# keyMANDevices.net
KiCad netlist of a schematic drawn in Altium Designer
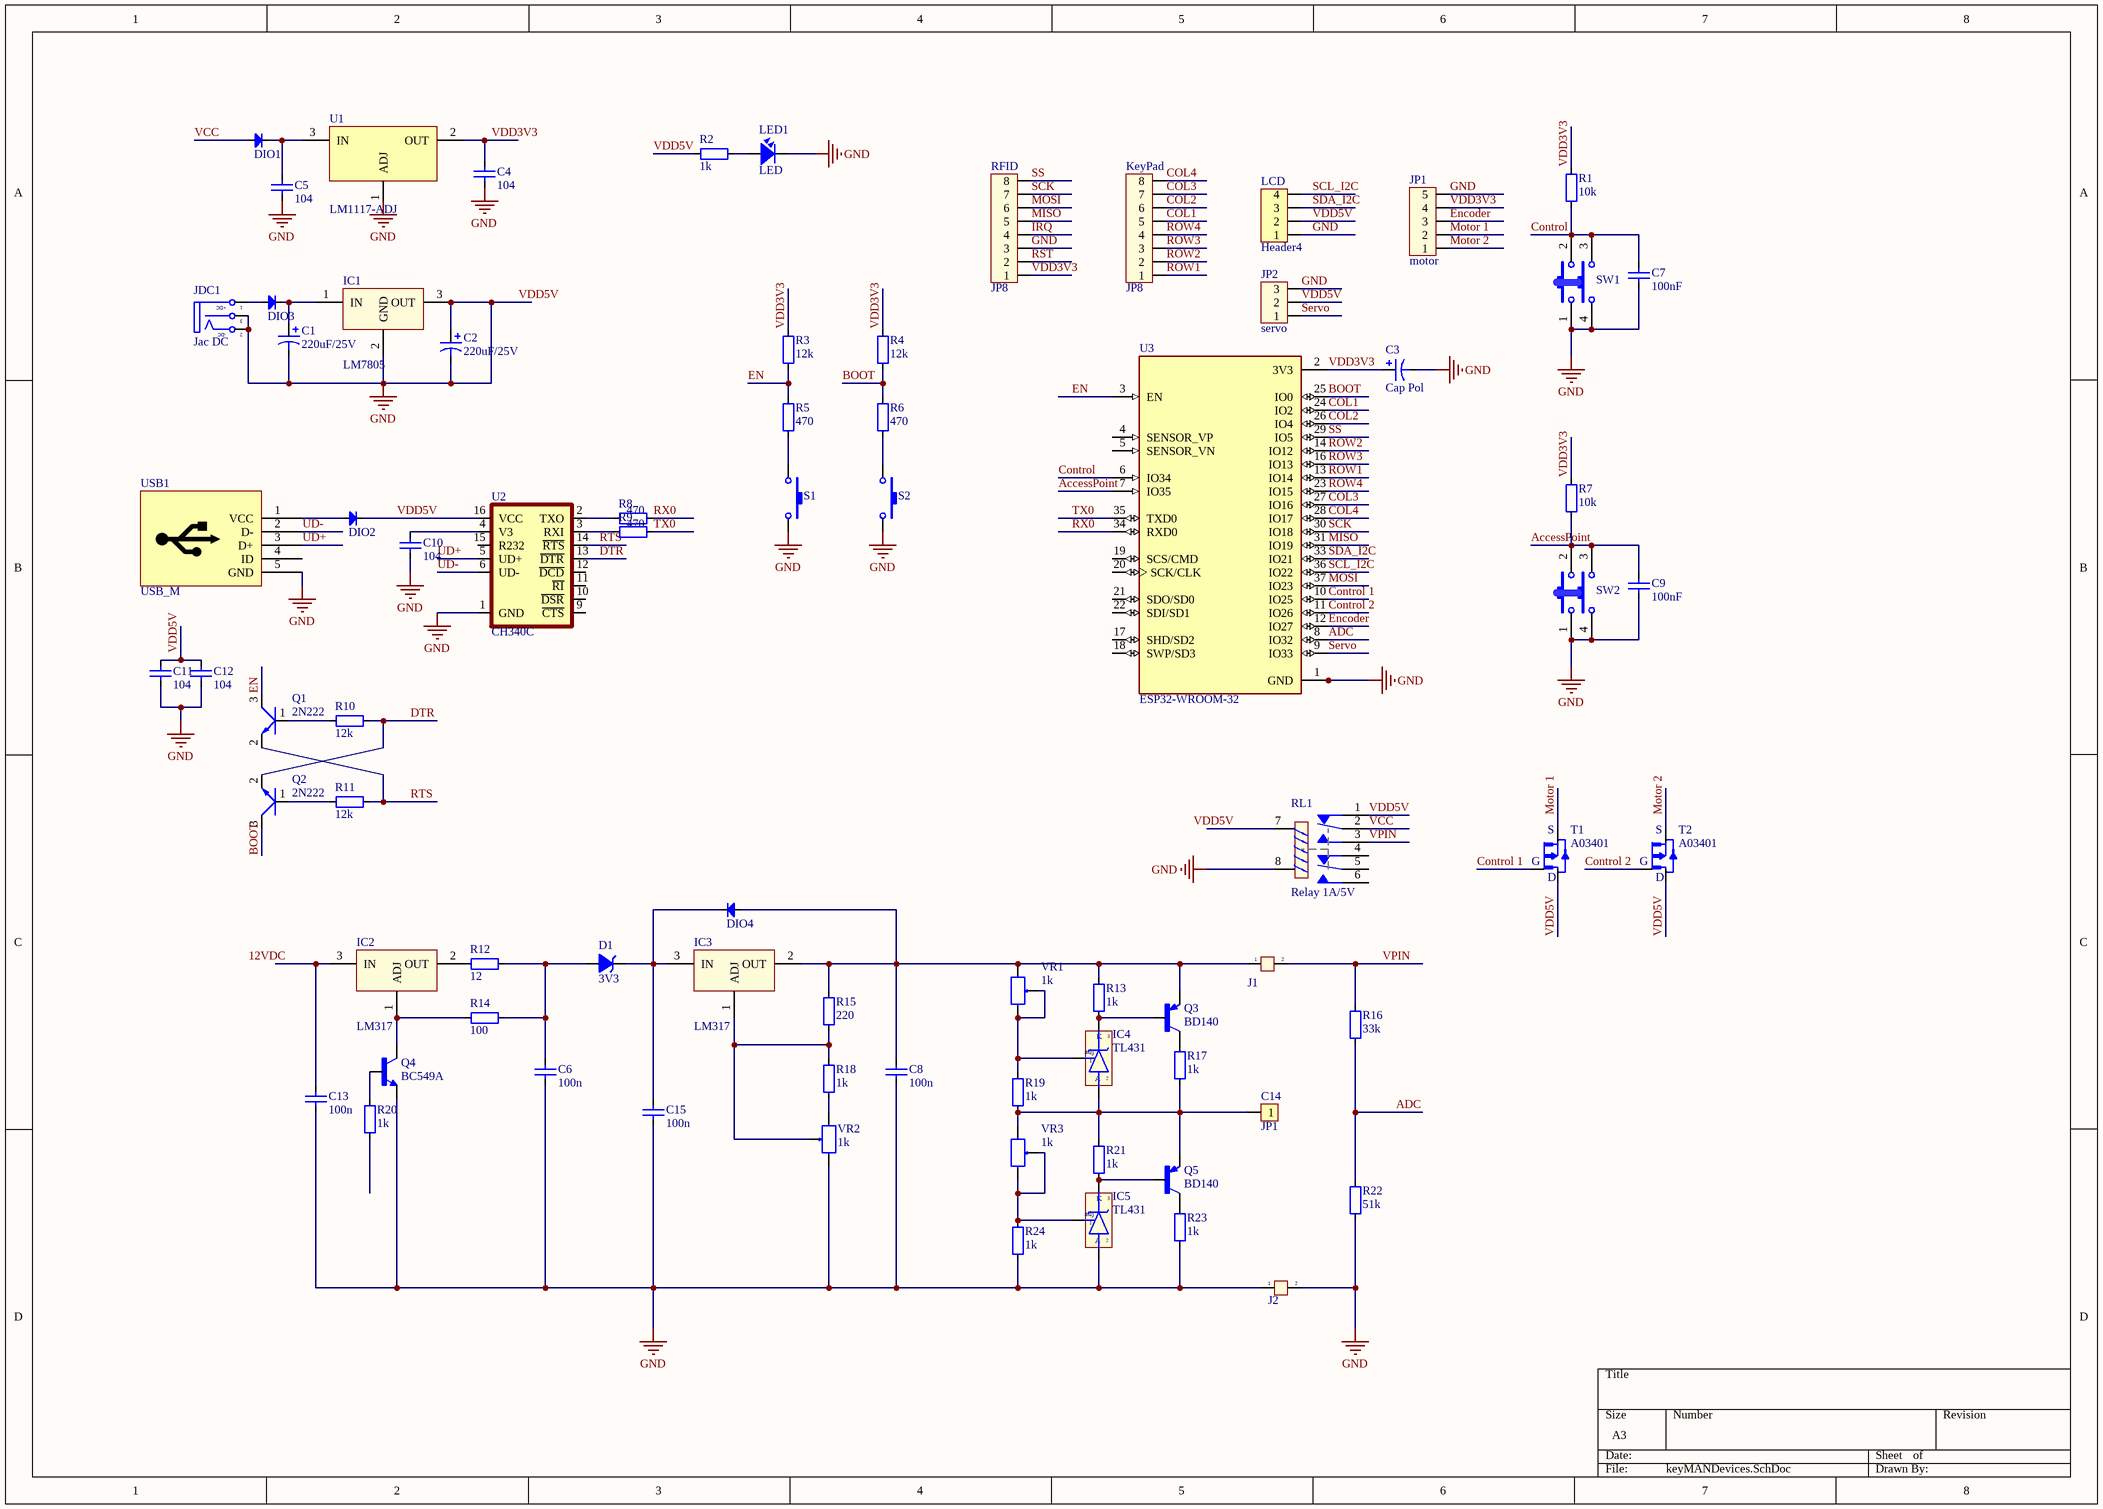
[diagram p0: keyMANDevices.SchDoc]

(export (version "E")
  (design (tool "Eeschema 10.0.6"))
  (components
    (comp (ref "C1")
      (value "220uF/25V")
      (footprint "C3MM")
      (description "Polarized Capacitor (Axial)")
      (fields (field (name "PUBLISHER") "Altium Limited"))
      (libsource (lib "My Library") (part "Cap Pol"))
    )
    (comp (ref "C2")
      (value "220uF/25V")
      (footprint "C3MM")
      (description "Polarized Capacitor (Axial)")
      (fields (field (name "PUBLISHER") "Altium Limited"))
      (libsource (lib "My Library") (part "Cap Pol"))
    )
    (comp (ref "C3")
      (value "Cap Pol")
      (footprint "C3MM")
      (description "Polarized Capacitor (Axial)")
      (fields (field (name "PUBLISHER") "Altium Limited"))
      (libsource (lib "My Library") (part "Cap Pol"))
    )
    (comp (ref "C4")
      (value "104")
      (footprint "CAP_0805")
      (description "Capacitor")
      (fields (field (name "PUBLISHER") "Altium Limited"))
      (libsource (lib "My Library") (part "CapSMD"))
    )
    (comp (ref "C5")
      (value "104")
      (footprint "CAP_0805")
      (description "Capacitor")
      (fields (field (name "PUBLISHER") "Altium Limited"))
      (libsource (lib "My Library") (part "CapSMD"))
    )
    (comp (ref "C6")
      (value "100n")
      (footprint "CAP_0402")
      (description "Capacitor")
      (fields (field (name "PUBLISHER") "Altium Limited"))
      (libsource (lib "My Library") (part "CapSMD"))
    )
    (comp (ref "C7")
      (value "100nF")
      (footprint "CAP_0402")
      (description "Capacitor")
      (fields (field (name "PUBLISHER") "Altium Limited"))
      (libsource (lib "My Library") (part "CapSMD"))
    )
    (comp (ref "C8")
      (value "100n")
      (footprint "CAP_0402")
      (description "Capacitor")
      (fields (field (name "PUBLISHER") "Altium Limited"))
      (libsource (lib "My Library") (part "CapSMD"))
    )
    (comp (ref "C9")
      (value "100nF")
      (footprint "CAP_0402")
      (description "Capacitor")
      (fields (field (name "PUBLISHER") "Altium Limited"))
      (libsource (lib "My Library") (part "CapSMD"))
    )
    (comp (ref "C10")
      (value "104")
      (footprint "CAP_0805")
      (description "Capacitor")
      (fields (field (name "PUBLISHER") "Altium Limited"))
      (libsource (lib "My Library") (part "CapSMD"))
    )
    (comp (ref "C11")
      (value "104")
      (footprint "CAP_0402")
      (description "Capacitor")
      (fields (field (name "PUBLISHER") "Altium Limited"))
      (libsource (lib "My Library") (part "CapSMD"))
    )
    (comp (ref "C12")
      (value "104")
      (footprint "CAP_0805")
      (description "Capacitor")
      (fields (field (name "PUBLISHER") "Altium Limited"))
      (libsource (lib "My Library") (part "CapSMD"))
    )
    (comp (ref "C13")
      (value "100n")
      (footprint "CAP_0402")
      (description "Capacitor")
      (fields (field (name "PUBLISHER") "Altium Limited"))
      (libsource (lib "My Library") (part "CapSMD"))
    )
    (comp (ref "C14")
      (value "JP1")
      (footprint "JP1-D1T")
      (description "WR-PHD 2.54 mm Angled Socket Header")
      (fields
        (field (name "MANUFACTURER") "Würth Elektronik eiSos GmbH")
        (field (name "PARTNO") "613002143121")
        (field (name "CREATED BY") "Karrer Zheng")
      )
      (libsource (lib "My Library") (part "JP1"))
    )
    (comp (ref "C15")
      (value "100n")
      (footprint "CAP_0402")
      (description "Capacitor")
      (fields (field (name "PUBLISHER") "Altium Limited"))
      (libsource (lib "My Library") (part "CapSMD"))
    )
    (comp (ref "D1")
      (value "3V3")
      (footprint "DZ0.5A")
      (description "Diode Zenner")
      (libsource (lib "My Library") (part "DZ"))
    )
    (comp (ref "DIO1")
      (value "Diode SMD")
      (footprint "DIO-SMD-106")
      (description "Default Diode")
      (fields (field (name "PUBLISHER") "Altium Limited"))
      (libsource (lib "My Library") (part "Diode SMD"))
    )
    (comp (ref "DIO2")
      (value "Diode SMD")
      (footprint "DIO-SMD-106")
      (description "Default Diode")
      (fields (field (name "PUBLISHER") "Altium Limited"))
      (libsource (lib "My Library") (part "Diode SMD"))
    )
    (comp (ref "DIO3")
      (value "Diode SMD")
      (footprint "DIO-SMD-106")
      (description "Default Diode")
      (fields (field (name "PUBLISHER") "Altium Limited"))
      (libsource (lib "My Library") (part "Diode SMD"))
    )
    (comp (ref "DIO4")
      (value "Diode SMD")
      (footprint "DIO-SMD-106")
      (description "Default Diode")
      (fields (field (name "PUBLISHER") "Altium Limited"))
      (libsource (lib "My Library") (part "Diode SMD"))
    )
    (comp (ref "IC1")
      (value "LM7805")
      (footprint "QTO-220")
      (description "On ap +, from + 5 to + 24VDC")
      (libsource (lib "My Library") (part "LM78xx"))
    )
    (comp (ref "IC2")
      (value "LM317")
      (footprint "QTO-220")
      (description "Adj Voltage +1.2 -> +37V")
      (libsource (lib "My Library") (part "LM317"))
    )
    (comp (ref "IC3")
      (value "LM317")
      (footprint "QTO-220")
      (description "Adj Voltage +1.2 -> +37V")
      (libsource (lib "My Library") (part "LM317"))
    )
    (comp (ref "IC4")
      (value "TL431")
      (footprint "qto-92")
      (description "Programmable Shunt Regulator")
      (libsource (lib "My Library") (part "TL431"))
    )
    (comp (ref "IC5")
      (value "TL431")
      (footprint "qto-92")
      (description "Programmable Shunt Regulator")
      (libsource (lib "My Library") (part "TL431"))
    )
    (comp (ref "J1") (value "Jumper 2") (footprint "jp2h") (libsource (lib "My Library") (part "JP 2")))
    (comp (ref "J2") (value "Jumper 2") (footprint "jp2h") (libsource (lib "My Library") (part "JP 2")))
    (comp (ref "JDC1")
      (value "Jac DC")
      (footprint "DC-IN")
      (description "Jac DC input")
      (libsource (lib "My Library") (part "DCIN"))
    )
    (comp (ref "JP1")
      (value "motor")
      (footprint "CON5")
      (description "Connector 5")
      (libsource (lib "My Library") (part "Con5"))
    )
    (comp (ref "JP2")
      (value "servo")
      (footprint "CON3")
      (description "Connector 3")
      (libsource (lib "My Library") (part "Con3"))
    )
    (comp (ref "KeyPad")
      (value "JP8")
      (footprint "Header8")
      (description "Connector 8")
      (libsource (lib "My Library") (part "Header8"))
    )
    (comp (ref "LCD")
      (value "Header4")
      (footprint "HDR4")
      (description "Header IDC, 4 x 1 Pin Vertical 2.54mm Pitch (Non-Boxed, Male)")
      (fields
        (field (name "MANUFACTURER") "Würth Elektronik eiSos GmbH")
        (field (name "PARTNO") "613002143121")
        (field (name "CREATED BY") "Karrer Zheng")
      )
      (libsource (lib "My Library") (part "Header4"))
    )
    (comp (ref "LED1")
      (value "LED")
      (footprint "LED-0805-Red")
      (description "LED Single colour Green and Red")
      (libsource (lib "My Library") (part "LED"))
    )
    (comp (ref "Q1")
      (value "2N222")
      (footprint "SOT23D")
      (description "NPN 600mW, ECB")
      (libsource (lib "My Library") (part "2N222"))
    )
    (comp (ref "Q2")
      (value "2N222")
      (footprint "SOT23D")
      (description "NPN 600mW, ECB")
      (libsource (lib "My Library") (part "2N222"))
    )
    (comp (ref "Q3")
      (value "BD140")
      (footprint "TO245P780X300X1364-3")
      (description "TRANS PNP 80V 1.5A SOT-32")
      (libsource (lib "BD140") (part "BD140"))
    )
    (comp (ref "Q4")
      (value "BC549A")
      (footprint "TO92250P510H770-3")
      (description "TO-92 30V 0.1A NPN Bipolar Transistor")
      (fields (field (name "MF") "Taiwan Semiconductor"))
      (libsource (lib "BC549A") (part "BC549A"))
    )
    (comp (ref "Q5")
      (value "BD140")
      (footprint "TO245P780X300X1364-3")
      (description "TRANS PNP 80V 1.5A SOT-32")
      (libsource (lib "BD140") (part "BD140"))
    )
    (comp (ref "R1")
      (value "10k")
      (footprint "RES-SMD-0805")
      (description "Resistor")
      (fields
        (field (name "MANUFACTURER") "Generic Components")
        (field (name "PUBLISHER") "Altium Hobart Technology Centre")
      )
      (libsource (lib "My Library") (part "Resistor - SMD"))
    )
    (comp (ref "R2")
      (value "1k")
      (footprint "RES-SMD-0805")
      (description "Resistor")
      (fields
        (field (name "MANUFACTURER") "Generic Components")
        (field (name "PUBLISHER") "Altium Hobart Technology Centre")
      )
      (libsource (lib "My Library") (part "Resistor - SMD"))
    )
    (comp (ref "R3")
      (value "12k")
      (footprint "RES-SMD-0805")
      (description "Resistor")
      (fields
        (field (name "MANUFACTURER") "Generic Components")
        (field (name "PUBLISHER") "Altium Hobart Technology Centre")
      )
      (libsource (lib "My Library") (part "Resistor - SMD"))
    )
    (comp (ref "R4")
      (value "12k")
      (footprint "RES-SMD-0805")
      (description "Resistor")
      (fields
        (field (name "MANUFACTURER") "Generic Components")
        (field (name "PUBLISHER") "Altium Hobart Technology Centre")
      )
      (libsource (lib "My Library") (part "Resistor - SMD"))
    )
    (comp (ref "R5")
      (value "470")
      (footprint "RES-SMD-0805")
      (description "Resistor")
      (fields
        (field (name "MANUFACTURER") "Generic Components")
        (field (name "PUBLISHER") "Altium Hobart Technology Centre")
      )
      (libsource (lib "My Library") (part "Resistor - SMD"))
    )
    (comp (ref "R6")
      (value "470")
      (footprint "RES-SMD-0805")
      (description "Resistor")
      (fields
        (field (name "MANUFACTURER") "Generic Components")
        (field (name "PUBLISHER") "Altium Hobart Technology Centre")
      )
      (libsource (lib "My Library") (part "Resistor - SMD"))
    )
    (comp (ref "R7")
      (value "10k")
      (footprint "RES-SMD-0805")
      (description "Resistor")
      (fields
        (field (name "MANUFACTURER") "Generic Components")
        (field (name "PUBLISHER") "Altium Hobart Technology Centre")
      )
      (libsource (lib "My Library") (part "Resistor - SMD"))
    )
    (comp (ref "R8")
      (value "470")
      (footprint "RES-SMD-0805")
      (description "Resistor")
      (fields
        (field (name "MANUFACTURER") "Generic Components")
        (field (name "PUBLISHER") "Altium Hobart Technology Centre")
      )
      (libsource (lib "My Library") (part "Resistor - SMD"))
    )
    (comp (ref "R9")
      (value "470")
      (footprint "RES-SMD-0805")
      (description "Resistor")
      (fields
        (field (name "MANUFACTURER") "Generic Components")
        (field (name "PUBLISHER") "Altium Hobart Technology Centre")
      )
      (libsource (lib "My Library") (part "Resistor - SMD"))
    )
    (comp (ref "R10")
      (value "12k")
      (footprint "RES-SMD-0805")
      (description "Resistor")
      (fields
        (field (name "MANUFACTURER") "Generic Components")
        (field (name "PUBLISHER") "Altium Hobart Technology Centre")
      )
      (libsource (lib "My Library") (part "Resistor - SMD"))
    )
    (comp (ref "R11")
      (value "12k")
      (footprint "RES-SMD-0805")
      (description "Resistor")
      (fields
        (field (name "MANUFACTURER") "Generic Components")
        (field (name "PUBLISHER") "Altium Hobart Technology Centre")
      )
      (libsource (lib "My Library") (part "Resistor - SMD"))
    )
    (comp (ref "R12")
      (value "12")
      (footprint "RES-SMD-0101")
      (description "Resistor")
      (fields
        (field (name "MANUFACTURER") "Generic Components")
        (field (name "PUBLISHER") "Altium Hobart Technology Centre")
      )
      (libsource (lib "My Library") (part "Resistor - SMD"))
    )
    (comp (ref "R13")
      (value "1k")
      (footprint "RES-SMD-0101")
      (description "Resistor")
      (fields
        (field (name "MANUFACTURER") "Generic Components")
        (field (name "PUBLISHER") "Altium Hobart Technology Centre")
      )
      (libsource (lib "My Library") (part "Resistor - SMD"))
    )
    (comp (ref "R14")
      (value "100")
      (footprint "RES-SMD-0101")
      (description "Resistor")
      (fields
        (field (name "MANUFACTURER") "Generic Components")
        (field (name "PUBLISHER") "Altium Hobart Technology Centre")
      )
      (libsource (lib "My Library") (part "Resistor - SMD"))
    )
    (comp (ref "R15")
      (value "220")
      (footprint "RES-SMD-0101")
      (description "Resistor")
      (fields
        (field (name "MANUFACTURER") "Generic Components")
        (field (name "PUBLISHER") "Altium Hobart Technology Centre")
      )
      (libsource (lib "My Library") (part "Resistor - SMD"))
    )
    (comp (ref "R16")
      (value "33k")
      (footprint "RES-SMD-0101")
      (description "Resistor")
      (fields
        (field (name "MANUFACTURER") "Generic Components")
        (field (name "PUBLISHER") "Altium Hobart Technology Centre")
      )
      (libsource (lib "My Library") (part "Resistor - SMD"))
    )
    (comp (ref "R17")
      (value "1k")
      (footprint "RES-SMD-0101")
      (description "Resistor")
      (fields
        (field (name "MANUFACTURER") "Generic Components")
        (field (name "PUBLISHER") "Altium Hobart Technology Centre")
      )
      (libsource (lib "My Library") (part "Resistor - SMD"))
    )
    (comp (ref "R18")
      (value "1k")
      (footprint "RES-SMD-0101")
      (description "Resistor")
      (fields
        (field (name "MANUFACTURER") "Generic Components")
        (field (name "PUBLISHER") "Altium Hobart Technology Centre")
      )
      (libsource (lib "My Library") (part "Resistor - SMD"))
    )
    (comp (ref "R19")
      (value "1k")
      (footprint "RES-SMD-0101")
      (description "Resistor")
      (fields
        (field (name "MANUFACTURER") "Generic Components")
        (field (name "PUBLISHER") "Altium Hobart Technology Centre")
      )
      (libsource (lib "My Library") (part "Resistor - SMD"))
    )
    (comp (ref "R20")
      (value "1k")
      (footprint "RES-SMD-0101")
      (description "Resistor")
      (fields
        (field (name "MANUFACTURER") "Generic Components")
        (field (name "PUBLISHER") "Altium Hobart Technology Centre")
      )
      (libsource (lib "My Library") (part "Resistor - SMD"))
    )
    (comp (ref "R21")
      (value "1k")
      (footprint "RES-SMD-0101")
      (description "Resistor")
      (fields
        (field (name "MANUFACTURER") "Generic Components")
        (field (name "PUBLISHER") "Altium Hobart Technology Centre")
      )
      (libsource (lib "My Library") (part "Resistor - SMD"))
    )
    (comp (ref "R22")
      (value "51k")
      (footprint "RES-SMD-0101")
      (description "Resistor")
      (fields
        (field (name "MANUFACTURER") "Generic Components")
        (field (name "PUBLISHER") "Altium Hobart Technology Centre")
      )
      (libsource (lib "My Library") (part "Resistor - SMD"))
    )
    (comp (ref "R23")
      (value "1k")
      (footprint "RES-SMD-0101")
      (description "Resistor")
      (fields
        (field (name "MANUFACTURER") "Generic Components")
        (field (name "PUBLISHER") "Altium Hobart Technology Centre")
      )
      (libsource (lib "My Library") (part "Resistor - SMD"))
    )
    (comp (ref "R24")
      (value "1k")
      (footprint "RES-SMD-0101")
      (description "Resistor")
      (fields
        (field (name "MANUFACTURER") "Generic Components")
        (field (name "PUBLISHER") "Altium Hobart Technology Centre")
      )
      (libsource (lib "My Library") (part "Resistor - SMD"))
    )
    (comp (ref "RFID")
      (value "JP8")
      (footprint "Header8")
      (description "Connector 8")
      (libsource (lib "My Library") (part "Header8"))
    )
    (comp (ref "RL1")
      (value "Relay 1A/5V")
      (footprint "RL_DPDT_1A")
      (description "Relay DPDT")
      (libsource (lib "My Library") (part "Relay 2"))
    )
    (comp (ref "S1")
      (value "SW-SMD")
      (footprint "SW 3x2x4")
      (description "Switch")
      (fields (field (name "PUBLISHER") "Altium Limited"))
      (libsource (lib "My Library") (part "SW-SMD"))
    )
    (comp (ref "S2")
      (value "SW-SMD")
      (footprint "SW 3x2x4")
      (description "Switch")
      (fields (field (name "PUBLISHER") "Altium Limited"))
      (libsource (lib "My Library") (part "SW-SMD"))
    )
    (comp (ref "SW1")
      (value "SW-4P-S")
      (footprint "SW-4P-S")
      (description "Switch Small 4 Pin")
      (fields (field (name "PUBLISHER") "Altium Limited"))
      (libsource (lib "My Library") (part "SW-4PIN-SMALL"))
    )
    (comp (ref "SW2")
      (value "SW-4P-S")
      (footprint "SW-4P-S")
      (description "Switch Small 4 Pin")
      (fields (field (name "PUBLISHER") "Altium Limited"))
      (libsource (lib "My Library") (part "SW-4PIN-SMALL"))
    )
    (comp (ref "T1")
      (value "A03401")
      (footprint "My Library:A3401")
      (description "P-Channel 30V 4A _Ta_ 1.4W _Ta_ Surface Mount SOT-23-3")
      (libsource (lib "My Library") (part "A03401"))
    )
    (comp (ref "T2")
      (value "A03401")
      (footprint "My Library:A3401")
      (description "P-Channel 30V 4A _Ta_ 1.4W _Ta_ Surface Mount SOT-23-3")
      (libsource (lib "My Library") (part "A03401"))
    )
    (comp (ref "U1")
      (value "LM1117-ADJ")
      (footprint "LM1117-SOP")
      (description "800mA Low-Dropout Linear Regulator")
      (fields (field (name "CREATOR") "Nguyen Ba Bien"))
      (libsource (lib "My Library") (part "LM1117-ADJ"))
    )
    (comp (ref "U2")
      (value "CH340C")
      (footprint "SO016")
      (description "USB to serial chip CH340")
      (fields (field (name "MF") "WCH"))
      (libsource (lib "My Library") (part "CH340C"))
    )
    (comp (ref "U3")
      (value "ESP32-WROOM-32")
      (footprint "MODULE_ESP32-WROOM-32")
      (description "Bluetooth, WiFi Transceiver Module 2.4GHz ~ 2.5GHz Surface Mount")
      (fields (field (name "MF") "Espressif Systems") (field (name "DIGI-KEY_PART_NUMBER") "1904-1010-1-ND"))
      (libsource (lib "My Library") (part "ESP32-WROOM-32"))
    )
    (comp (ref "USB1")
      (value "USB_M")
      (footprint "USB_B_MINI_SMD")
      (libsource (lib "My Library") (part "USB_M"))
    )
    (comp (ref "VR1")
      (value "1k")
      (footprint "VR")
      (description "Var Resistor")
      (libsource (lib "My Library") (part "VR_1"))
    )
    (comp (ref "VR2")
      (value "1k")
      (footprint "VR")
      (description "Var Resistor")
      (libsource (lib "My Library") (part "VR_1"))
    )
    (comp (ref "VR3")
      (value "1k")
      (footprint "VR")
      (description "Var Resistor")
      (libsource (lib "My Library") (part "VR_1"))
    )
  )
  (nets
    (net (code "2") (name "/ADC") (class "Default")
      (node (ref "R16") (pin "1") (pinfunction "1_1") (pintype "passive"))
      (node (ref "R22") (pin "2") (pinfunction "2_2") (pintype "passive"))
      (node (ref "U3") (pin "8") (pinfunction "IO32_8") (pintype "bidirectional"))
    )
    (net (code "3") (name "/AccessPoint") (class "Default")
      (node (ref "C9") (pin "2") (pinfunction "2_2") (pintype "passive"))
      (node (ref "R7") (pin "2") (pinfunction "2_2") (pintype "passive"))
      (node (ref "SW2") (pin "2") (pinfunction "2_2") (pintype "passive"))
      (node (ref "SW2") (pin "3") (pinfunction "3_3") (pintype "passive"))
      (node (ref "U3") (pin "7") (pinfunction "IO35_7") (pintype "input"))
    )
    (net (code "4") (name "/BOOT") (class "Default")
      (node (ref "Q2") (pin "3") (pinfunction "C_3") (pintype "passive"))
      (node (ref "R4") (pin "1") (pinfunction "1_1") (pintype "passive"))
      (node (ref "R6") (pin "2") (pinfunction "2_2") (pintype "passive"))
      (node (ref "U3") (pin "25") (pinfunction "IO0_25") (pintype "bidirectional"))
    )
    (net (code "5") (name "/COL1") (class "Default")
      (node (ref "KeyPad") (pin "5") (pinfunction "5_5") (pintype "passive"))
      (node (ref "U3") (pin "24") (pinfunction "IO2_24") (pintype "bidirectional"))
    )
    (net (code "6") (name "/COL2") (class "Default")
      (node (ref "KeyPad") (pin "6") (pinfunction "6_6") (pintype "passive"))
      (node (ref "U3") (pin "26") (pinfunction "IO4_26") (pintype "bidirectional"))
    )
    (net (code "7") (name "/COL3") (class "Default")
      (node (ref "KeyPad") (pin "7") (pinfunction "7_7") (pintype "passive"))
      (node (ref "U3") (pin "27") (pinfunction "IO16_27") (pintype "bidirectional"))
    )
    (net (code "8") (name "/COL4") (class "Default")
      (node (ref "KeyPad") (pin "8") (pinfunction "8_8") (pintype "passive"))
      (node (ref "U3") (pin "28") (pinfunction "IO17_28") (pintype "bidirectional"))
    )
    (net (code "9") (name "/Control") (class "Default")
      (node (ref "C7") (pin "2") (pinfunction "2_2") (pintype "passive"))
      (node (ref "R1") (pin "2") (pinfunction "2_2") (pintype "passive"))
      (node (ref "SW1") (pin "2") (pinfunction "2_2") (pintype "passive"))
      (node (ref "SW1") (pin "3") (pinfunction "3_3") (pintype "passive"))
      (node (ref "U3") (pin "6") (pinfunction "IO34_6") (pintype "input"))
    )
    (net (code "10") (name "/Control 1") (class "Default")
      (node (ref "T1") (pin "1") (pinfunction "G_1") (pintype "passive"))
      (node (ref "U3") (pin "10") (pinfunction "IO25_10") (pintype "bidirectional"))
    )
    (net (code "11") (name "/Control 2") (class "Default")
      (node (ref "T2") (pin "1") (pinfunction "G_1") (pintype "passive"))
      (node (ref "U3") (pin "11") (pinfunction "IO26_11") (pintype "bidirectional"))
    )
    (net (code "12") (name "/DTR") (class "Default")
      (node (ref "Q2") (pin "2") (pinfunction "E_2") (pintype "passive"))
      (node (ref "R10") (pin "2") (pinfunction "2_2") (pintype "passive"))
      (node (ref "U2") (pin "13") (pinfunction "~{DTR}_13") (pintype "bidirectional"))
    )
    (net (code "13") (name "/EN") (class "Default")
      (node (ref "Q1") (pin "3") (pinfunction "C_3") (pintype "passive"))
      (node (ref "R3") (pin "1") (pinfunction "1_1") (pintype "passive"))
      (node (ref "R5") (pin "2") (pinfunction "2_2") (pintype "passive"))
      (node (ref "U3") (pin "3") (pinfunction "EN_3") (pintype "input"))
    )
    (net (code "14") (name "/Encoder") (class "Default")
      (node (ref "JP1") (pin "3") (pinfunction "3_3") (pintype "passive"))
      (node (ref "U3") (pin "12") (pinfunction "IO27_12") (pintype "bidirectional"))
    )
    (net (code "15") (name "/IRQ") (class "Default")
      (node (ref "RFID") (pin "4") (pinfunction "4_4") (pintype "passive"))
    )
    (net (code "16") (name "/MISO") (class "Default")
      (node (ref "RFID") (pin "5") (pinfunction "5_5") (pintype "passive"))
      (node (ref "U3") (pin "31") (pinfunction "IO19_31") (pintype "bidirectional"))
    )
    (net (code "17") (name "/MOSI") (class "Default")
      (node (ref "RFID") (pin "6") (pinfunction "6_6") (pintype "passive"))
      (node (ref "U3") (pin "37") (pinfunction "IO23_37") (pintype "bidirectional"))
    )
    (net (code "18") (name "/Motor 1") (class "Default")
      (node (ref "JP1") (pin "2") (pinfunction "2_2") (pintype "passive"))
      (node (ref "T1") (pin "2") (pinfunction "S_2") (pintype "passive"))
    )
    (net (code "19") (name "/Motor 2") (class "Default")
      (node (ref "JP1") (pin "1") (pinfunction "1_1") (pintype "passive"))
      (node (ref "T2") (pin "2") (pinfunction "S_2") (pintype "passive"))
    )
    (net (code "20") (name "/ROW1") (class "Default")
      (node (ref "KeyPad") (pin "1") (pinfunction "1_1") (pintype "passive"))
      (node (ref "U3") (pin "13") (pinfunction "IO14_13") (pintype "bidirectional"))
    )
    (net (code "21") (name "/ROW2") (class "Default")
      (node (ref "KeyPad") (pin "2") (pinfunction "2_2") (pintype "passive"))
      (node (ref "U3") (pin "14") (pinfunction "IO12_14") (pintype "bidirectional"))
    )
    (net (code "22") (name "/ROW3") (class "Default")
      (node (ref "KeyPad") (pin "3") (pinfunction "3_3") (pintype "passive"))
      (node (ref "U3") (pin "16") (pinfunction "IO13_16") (pintype "bidirectional"))
    )
    (net (code "23") (name "/ROW4") (class "Default")
      (node (ref "KeyPad") (pin "4") (pinfunction "4_4") (pintype "passive"))
      (node (ref "U3") (pin "23") (pinfunction "IO15_23") (pintype "bidirectional"))
    )
    (net (code "24") (name "/RST") (class "Default")
      (node (ref "RFID") (pin "2") (pinfunction "2_2") (pintype "passive"))
    )
    (net (code "25") (name "/RTS") (class "Default")
      (node (ref "Q1") (pin "2") (pinfunction "E_2") (pintype "passive"))
      (node (ref "R11") (pin "2") (pinfunction "2_2") (pintype "passive"))
      (node (ref "U2") (pin "14") (pinfunction "~{RTS}_14") (pintype "bidirectional"))
    )
    (net (code "26") (name "/RX0") (class "Default")
      (node (ref "R8") (pin "2") (pinfunction "2_2") (pintype "passive"))
      (node (ref "U3") (pin "34") (pinfunction "RXD0_34") (pintype "bidirectional"))
    )
    (net (code "27") (name "/SCK") (class "Default")
      (node (ref "RFID") (pin "7") (pinfunction "7_7") (pintype "passive"))
      (node (ref "U3") (pin "30") (pinfunction "IO18_30") (pintype "bidirectional"))
    )
    (net (code "28") (name "/SCL_I2C") (class "Default")
      (node (ref "LCD") (pin "4") (pinfunction "4_4") (pintype "passive"))
      (node (ref "U3") (pin "36") (pinfunction "IO22_36") (pintype "bidirectional"))
    )
    (net (code "29") (name "/SDA_I2C") (class "Default")
      (node (ref "LCD") (pin "3") (pinfunction "3_3") (pintype "passive"))
      (node (ref "U3") (pin "33") (pinfunction "IO21_33") (pintype "bidirectional"))
    )
    (net (code "30") (name "/SS") (class "Default")
      (node (ref "RFID") (pin "8") (pinfunction "8_8") (pintype "passive"))
      (node (ref "U3") (pin "29") (pinfunction "IO5_29") (pintype "bidirectional"))
    )
    (net (code "31") (name "/Servo") (class "Default")
      (node (ref "JP2") (pin "1") (pinfunction "1_1") (pintype "passive"))
      (node (ref "U3") (pin "9") (pinfunction "IO33_9") (pintype "bidirectional"))
    )
    (net (code "32") (name "/TX0") (class "Default")
      (node (ref "R9") (pin "2") (pinfunction "2_2") (pintype "passive"))
      (node (ref "U3") (pin "35") (pinfunction "TXD0_35") (pintype "bidirectional"))
    )
    (net (code "33") (name "/UD+") (class "Default")
      (node (ref "U2") (pin "5") (pinfunction "UD+_5") (pintype "bidirectional"))
      (node (ref "USB1") (pin "3") (pinfunction "D+_3") (pintype "passive"))
    )
    (net (code "34") (name "/UD-") (class "Default")
      (node (ref "U2") (pin "6") (pinfunction "UD-_6") (pintype "bidirectional"))
      (node (ref "USB1") (pin "2") (pinfunction "D-_2") (pintype "passive"))
    )
    (net (code "35") (name "/VCC") (class "Default")
      (node (ref "DIO1") (pin "1") (pinfunction "A_1") (pintype "passive"))
      (node (ref "RL1") (pin "2") (pinfunction "2_2") (pintype "passive"))
    )
    (net (code "36") (name "/VDD3V3") (class "Default")
      (node (ref "C3") (pin "1") (pinfunction "1_1") (pintype "passive"))
      (node (ref "C4") (pin "2") (pinfunction "2_2") (pintype "passive"))
      (node (ref "JP1") (pin "4") (pinfunction "4_4") (pintype "passive"))
      (node (ref "R1") (pin "1") (pinfunction "1_1") (pintype "passive"))
      (node (ref "R3") (pin "2") (pinfunction "2_2") (pintype "passive"))
      (node (ref "R4") (pin "2") (pinfunction "2_2") (pintype "passive"))
      (node (ref "R7") (pin "1") (pinfunction "1_1") (pintype "passive"))
      (node (ref "RFID") (pin "1") (pinfunction "1_1") (pintype "passive"))
      (node (ref "U1") (pin "2") (pinfunction "OUT_2") (pintype "passive"))
      (node (ref "U3") (pin "2") (pinfunction "3V3_2") (pintype "power_in"))
    )
    (net (code "37") (name "/VPIN") (class "Default")
      (node (ref "J1") (pin "2") (pinfunction "2_2") (pintype "passive"))
      (node (ref "R16") (pin "2") (pinfunction "2_2") (pintype "passive"))
      (node (ref "RL1") (pin "3") (pinfunction "3_3") (pintype "passive"))
    )
    (net (code "38") (name "GND") (class "Default")
      (node (ref "C1") (pin "2") (pinfunction "2_2") (pintype "passive"))
      (node (ref "C10") (pin "1") (pinfunction "1_1") (pintype "passive"))
      (node (ref "C11") (pin "1") (pinfunction "1_1") (pintype "passive"))
      (node (ref "C11") (pin "2") (pinfunction "2_2") (pintype "passive"))
      (node (ref "C12") (pin "1") (pinfunction "1_1") (pintype "passive"))
      (node (ref "C12") (pin "2") (pinfunction "2_2") (pintype "passive"))
      (node (ref "C13") (pin "1") (pinfunction "1_1") (pintype "passive"))
      (node (ref "C15") (pin "1") (pinfunction "1_1") (pintype "passive"))
      (node (ref "C2") (pin "1") (pinfunction "1_1") (pintype "passive"))
      (node (ref "C2") (pin "2") (pinfunction "2_2") (pintype "passive"))
      (node (ref "C3") (pin "2") (pinfunction "2_2") (pintype "passive"))
      (node (ref "C4") (pin "1") (pinfunction "1_1") (pintype "passive"))
      (node (ref "C5") (pin "1") (pinfunction "1_1") (pintype "passive"))
      (node (ref "C6") (pin "1") (pinfunction "1_1") (pintype "passive"))
      (node (ref "C7") (pin "1") (pinfunction "1_1") (pintype "passive"))
      (node (ref "C8") (pin "1") (pinfunction "1_1") (pintype "passive"))
      (node (ref "C9") (pin "1") (pinfunction "1_1") (pintype "passive"))
      (node (ref "DIO2") (pin "2") (pinfunction "K_2") (pintype "passive"))
      (node (ref "IC1") (pin "2") (pinfunction "GND_2") (pintype "passive"))
      (node (ref "IC1") (pin "3") (pinfunction "OUT_3") (pintype "passive"))
      (node (ref "IC5") (pin "2") (pinfunction "A_2") (pintype "passive"))
      (node (ref "J2") (pin "1") (pinfunction "1_1") (pintype "passive"))
      (node (ref "J2") (pin "2") (pinfunction "2_2") (pintype "passive"))
      (node (ref "JDC1") (pin "2") (pinfunction "TN_2") (pintype "passive"))
      (node (ref "JDC1") (pin "3") (pinfunction "S_3") (pintype "power_in"))
      (node (ref "JP1") (pin "5") (pinfunction "5_5") (pintype "passive"))
      (node (ref "JP2") (pin "2") (pinfunction "2_2") (pintype "passive"))
      (node (ref "JP2") (pin "3") (pinfunction "3_3") (pintype "passive"))
      (node (ref "LCD") (pin "1") (pinfunction "1_1") (pintype "passive"))
      (node (ref "LCD") (pin "2") (pinfunction "2_2") (pintype "passive"))
      (node (ref "LED1") (pin "2") (pinfunction "2_2") (pintype "passive"))
      (node (ref "Q4") (pin "3") (pinfunction "E_3") (pintype "passive"))
      (node (ref "R2") (pin "1") (pinfunction "1_1") (pintype "passive"))
      (node (ref "R22") (pin "1") (pinfunction "1_1") (pintype "passive"))
      (node (ref "R23") (pin "1") (pinfunction "1_1") (pintype "passive"))
      (node (ref "R24") (pin "1") (pinfunction "1_1") (pintype "passive"))
      (node (ref "RFID") (pin "3") (pinfunction "3_3") (pintype "passive"))
      (node (ref "RL1") (pin "1") (pinfunction "1_1") (pintype "passive"))
      (node (ref "RL1") (pin "8") (pinfunction "8_8") (pintype "passive"))
      (node (ref "S1") (pin "2") (pinfunction "2_2") (pintype "passive"))
      (node (ref "S2") (pin "2") (pinfunction "2_2") (pintype "passive"))
      (node (ref "SW1") (pin "1") (pinfunction "1_1") (pintype "passive"))
      (node (ref "SW1") (pin "4") (pinfunction "4_4") (pintype "passive"))
      (node (ref "SW2") (pin "1") (pinfunction "1_1") (pintype "passive"))
      (node (ref "SW2") (pin "4") (pinfunction "4_4") (pintype "passive"))
      (node (ref "T1") (pin "3") (pinfunction "D_3") (pintype "passive"))
      (node (ref "T2") (pin "3") (pinfunction "D_3") (pintype "passive"))
      (node (ref "U1") (pin "1") (pinfunction "ADJ_1") (pintype "passive"))
      (node (ref "U2") (pin "1") (pinfunction "GND_1") (pintype "bidirectional"))
      (node (ref "U2") (pin "16") (pinfunction "VCC_16") (pintype "bidirectional"))
      (node (ref "U3") (pin "1") (pinfunction "GND_1") (pintype "power_in"))
      (node (ref "U3") (pin "15") (pinfunction "GND_15") (pintype "power_in"))
      (node (ref "U3") (pin "38") (pinfunction "GND_38") (pintype "power_in"))
      (node (ref "U3") (pin "39_1") (pinfunction "GND_39_1") (pintype "power_in"))
      (node (ref "U3") (pin "39_10") (pinfunction "GND_39_10") (pintype "power_in"))
      (node (ref "U3") (pin "39_11") (pinfunction "GND_39_11") (pintype "power_in"))
      (node (ref "U3") (pin "39_12") (pinfunction "GND_39_12") (pintype "power_in"))
      (node (ref "U3") (pin "39_13") (pinfunction "GND_39_13") (pintype "power_in"))
      (node (ref "U3") (pin "39_14") (pinfunction "GND_39_14") (pintype "power_in"))
      (node (ref "U3") (pin "39_15") (pinfunction "GND_39_15") (pintype "power_in"))
      (node (ref "U3") (pin "39_16") (pinfunction "GND_39_16") (pintype "power_in"))
      (node (ref "U3") (pin "39_17") (pinfunction "GND_39_17") (pintype "power_in"))
      (node (ref "U3") (pin "39_18") (pinfunction "GND_39_18") (pintype "power_in"))
      (node (ref "U3") (pin "39_19") (pinfunction "GND_39_19") (pintype "power_in"))
      (node (ref "U3") (pin "39_2") (pinfunction "GND_39_2") (pintype "power_in"))
      (node (ref "U3") (pin "39_20") (pinfunction "GND_39_20") (pintype "power_in"))
      (node (ref "U3") (pin "39_21") (pinfunction "GND_39_21") (pintype "power_in"))
      (node (ref "U3") (pin "39_3") (pinfunction "GND_39_3") (pintype "power_in"))
      (node (ref "U3") (pin "39_4") (pinfunction "GND_39_4") (pintype "power_in"))
      (node (ref "U3") (pin "39_5") (pinfunction "GND_39_5") (pintype "power_in"))
      (node (ref "U3") (pin "39_6") (pinfunction "GND_39_6") (pintype "power_in"))
      (node (ref "U3") (pin "39_7") (pinfunction "GND_39_7") (pintype "power_in"))
      (node (ref "U3") (pin "39_8") (pinfunction "GND_39_8") (pintype "power_in"))
      (node (ref "U3") (pin "39_9") (pinfunction "GND_39_9") (pintype "power_in"))
      (node (ref "USB1") (pin "5") (pinfunction "GND_5") (pintype "passive"))
      (node (ref "VR2") (pin "1") (pinfunction "1_1") (pintype "passive"))
    )
    (net (code "39") (name "Net-(D1-A)") (class "Default")
      (node (ref "C6") (pin "2") (pinfunction "2_2") (pintype "passive"))
      (node (ref "D1") (pin "1") (pinfunction "A_1") (pintype "passive"))
      (node (ref "R12") (pin "2") (pinfunction "2_2") (pintype "passive"))
      (node (ref "R14") (pin "2") (pinfunction "2_2") (pintype "passive"))
    )
    (net (code "40") (name "Net-(D1-K)") (class "Default")
      (node (ref "C15") (pin "2") (pinfunction "2_2") (pintype "passive"))
      (node (ref "D1") (pin "2") (pinfunction "K_2") (pintype "passive"))
      (node (ref "DIO4") (pin "2") (pinfunction "K_2") (pintype "passive"))
      (node (ref "IC3") (pin "3") (pinfunction "IN_3") (pintype "passive"))
    )
    (net (code "41") (name "Net-(DIO1-K)") (class "Default")
      (node (ref "C5") (pin "2") (pinfunction "2_2") (pintype "passive"))
      (node (ref "DIO1") (pin "2") (pinfunction "K_2") (pintype "passive"))
      (node (ref "U1") (pin "3") (pinfunction "IN_3") (pintype "passive"))
    )
    (net (code "42") (name "Net-(DIO2-A)") (class "Default")
      (node (ref "DIO2") (pin "1") (pinfunction "A_1") (pintype "passive"))
      (node (ref "USB1") (pin "1") (pinfunction "VCC_1") (pintype "passive"))
    )
    (net (code "43") (name "Net-(DIO3-A)") (class "Default")
      (node (ref "DIO3") (pin "1") (pinfunction "A_1") (pintype "passive"))
      (node (ref "JDC1") (pin "1") (pinfunction "T_1") (pintype "passive"))
    )
    (net (code "44") (name "Net-(DIO3-K)") (class "Default")
      (node (ref "C1") (pin "1") (pinfunction "1_1") (pintype "passive"))
      (node (ref "DIO3") (pin "2") (pinfunction "K_2") (pintype "passive"))
      (node (ref "IC1") (pin "1") (pinfunction "IN_1") (pintype "passive"))
    )
    (net (code "45") (name "Net-(DIO4-A)") (class "Default")
      (node (ref "C8") (pin "2") (pinfunction "2_2") (pintype "passive"))
      (node (ref "DIO4") (pin "1") (pinfunction "A_1") (pintype "passive"))
      (node (ref "IC3") (pin "2") (pinfunction "OUT_2") (pintype "passive"))
      (node (ref "J1") (pin "1") (pinfunction "1_1") (pintype "passive"))
      (node (ref "Q3") (pin "1") (pinfunction "E_1") (pintype "passive"))
      (node (ref "R13") (pin "2") (pinfunction "2_2") (pintype "passive"))
      (node (ref "R15") (pin "2") (pinfunction "2_2") (pintype "passive"))
      (node (ref "VR1") (pin "1") (pinfunction "1_1") (pintype "passive"))
    )
    (net (code "46") (name "Net-(IC2-ADJ)") (class "Default")
      (node (ref "IC2") (pin "1") (pinfunction "ADJ_1") (pintype "passive"))
      (node (ref "Q4") (pin "1") (pinfunction "C_1") (pintype "passive"))
      (node (ref "R14") (pin "1") (pinfunction "1_1") (pintype "passive"))
    )
    (net (code "47") (name "Net-(IC2-IN)") (class "Default")
      (node (ref "C13") (pin "2") (pinfunction "2_2") (pintype "passive"))
      (node (ref "IC2") (pin "3") (pinfunction "IN_3") (pintype "passive"))
    )
    (net (code "48") (name "Net-(IC2-OUT)") (class "Default")
      (node (ref "IC2") (pin "2") (pinfunction "OUT_2") (pintype "passive"))
      (node (ref "R12") (pin "1") (pinfunction "1_1") (pintype "passive"))
    )
    (net (code "49") (name "Net-(IC3-ADJ)") (class "Default")
      (node (ref "IC3") (pin "1") (pinfunction "ADJ_1") (pintype "passive"))
      (node (ref "R15") (pin "1") (pinfunction "1_1") (pintype "passive"))
      (node (ref "R18") (pin "2") (pinfunction "2_2") (pintype "passive"))
      (node (ref "VR2") (pin "2") (pinfunction "2_2") (pintype "passive"))
    )
    (net (code "50") (name "Net-(IC4-A)") (class "Default")
      (node (ref "C14") (pin "1") (pinfunction "1_1") (pintype "passive"))
      (node (ref "IC4") (pin "2") (pinfunction "A_2") (pintype "passive"))
      (node (ref "Q5") (pin "1") (pinfunction "E_1") (pintype "passive"))
      (node (ref "R17") (pin "1") (pinfunction "1_1") (pintype "passive"))
      (node (ref "R19") (pin "1") (pinfunction "1_1") (pintype "passive"))
      (node (ref "R21") (pin "2") (pinfunction "2_2") (pintype "passive"))
      (node (ref "VR3") (pin "1") (pinfunction "1_1") (pintype "passive"))
    )
    (net (code "51") (name "Net-(IC4-K)") (class "Default")
      (node (ref "IC4") (pin "3") (pinfunction "K_3") (pintype "passive"))
      (node (ref "Q3") (pin "3") (pinfunction "B_3") (pintype "passive"))
      (node (ref "R13") (pin "1") (pinfunction "1_1") (pintype "passive"))
    )
    (net (code "52") (name "Net-(IC4-adj)") (class "Default")
      (node (ref "IC4") (pin "1") (pinfunction "adj_1") (pintype "passive"))
      (node (ref "R19") (pin "2") (pinfunction "2_2") (pintype "passive"))
      (node (ref "VR1") (pin "2") (pinfunction "2_2") (pintype "passive"))
      (node (ref "VR1") (pin "3") (pinfunction "3_3") (pintype "passive"))
    )
    (net (code "53") (name "Net-(IC5-K)") (class "Default")
      (node (ref "IC5") (pin "3") (pinfunction "K_3") (pintype "passive"))
      (node (ref "Q5") (pin "3") (pinfunction "B_3") (pintype "passive"))
      (node (ref "R21") (pin "1") (pinfunction "1_1") (pintype "passive"))
    )
    (net (code "54") (name "Net-(IC5-adj)") (class "Default")
      (node (ref "IC5") (pin "1") (pinfunction "adj_1") (pintype "passive"))
      (node (ref "R24") (pin "2") (pinfunction "2_2") (pintype "passive"))
      (node (ref "VR3") (pin "2") (pinfunction "2_2") (pintype "passive"))
      (node (ref "VR3") (pin "3") (pinfunction "3_3") (pintype "passive"))
    )
    (net (code "55") (name "Net-(LED1-Pad1)") (class "Default")
      (node (ref "LED1") (pin "1") (pinfunction "1_1") (pintype "passive"))
      (node (ref "R2") (pin "2") (pinfunction "2_2") (pintype "passive"))
    )
    (net (code "56") (name "Net-(Q1-B)") (class "Default")
      (node (ref "Q1") (pin "1") (pinfunction "B_1") (pintype "passive"))
      (node (ref "R10") (pin "1") (pinfunction "1_1") (pintype "passive"))
    )
    (net (code "57") (name "Net-(Q2-B)") (class "Default")
      (node (ref "Q2") (pin "1") (pinfunction "B_1") (pintype "passive"))
      (node (ref "R11") (pin "1") (pinfunction "1_1") (pintype "passive"))
    )
    (net (code "58") (name "Net-(Q3-C)") (class "Default")
      (node (ref "Q3") (pin "2") (pinfunction "C_2") (pintype "passive"))
      (node (ref "R17") (pin "2") (pinfunction "2_2") (pintype "passive"))
    )
    (net (code "59") (name "Net-(Q4-B)") (class "Default")
      (node (ref "Q4") (pin "2") (pinfunction "B_2") (pintype "passive"))
      (node (ref "R20") (pin "2") (pinfunction "2_2") (pintype "passive"))
    )
    (net (code "60") (name "Net-(Q5-C)") (class "Default")
      (node (ref "Q5") (pin "2") (pinfunction "C_2") (pintype "passive"))
      (node (ref "R23") (pin "2") (pinfunction "2_2") (pintype "passive"))
    )
    (net (code "61") (name "Net-(R5-Pad1)") (class "Default")
      (node (ref "R5") (pin "1") (pinfunction "1_1") (pintype "passive"))
      (node (ref "S1") (pin "1") (pinfunction "1_1") (pintype "passive"))
    )
    (net (code "62") (name "Net-(R6-Pad1)") (class "Default")
      (node (ref "R6") (pin "1") (pinfunction "1_1") (pintype "passive"))
      (node (ref "S2") (pin "1") (pinfunction "1_1") (pintype "passive"))
    )
    (net (code "63") (name "Net-(R18-Pad1)") (class "Default")
      (node (ref "R18") (pin "1") (pinfunction "1_1") (pintype "passive"))
      (node (ref "VR2") (pin "3") (pinfunction "3_3") (pintype "passive"))
    )
    (net (code "64") (name "Net-(U2-RXI)") (class "Default")
      (node (ref "R9") (pin "1") (pinfunction "1_1") (pintype "passive"))
      (node (ref "U2") (pin "3") (pinfunction "RXI_3") (pintype "bidirectional"))
    )
    (net (code "65") (name "Net-(U2-TXO)") (class "Default")
      (node (ref "R8") (pin "1") (pinfunction "1_1") (pintype "passive"))
      (node (ref "U2") (pin "2") (pinfunction "TXO_2") (pintype "bidirectional"))
    )
    (net (code "66") (name "Net-(U2-V3)") (class "Default")
      (node (ref "C10") (pin "2") (pinfunction "2_2") (pintype "passive"))
      (node (ref "U2") (pin "4") (pinfunction "V3_4") (pintype "bidirectional"))
    )
    (net (code "67") (name "unconnected-(R20-Pad1)") (class "Default")
      (node (ref "R20") (pin "1") (pinfunction "1_1") (pintype "passive"))
    )
    (net (code "68") (name "unconnected-(RL1-Pad4)") (class "Default")
      (node (ref "RL1") (pin "4") (pinfunction "4_4") (pintype "passive"))
    )
    (net (code "69") (name "unconnected-(RL1-Pad5)") (class "Default")
      (node (ref "RL1") (pin "5") (pinfunction "5_5") (pintype "passive"))
    )
    (net (code "70") (name "unconnected-(RL1-Pad6)") (class "Default")
      (node (ref "RL1") (pin "6") (pinfunction "6_6") (pintype "passive"))
    )
    (net (code "71") (name "unconnected-(RL1-Pad7)") (class "Default")
      (node (ref "RL1") (pin "7") (pinfunction "7_7") (pintype "passive"))
    )
    (net (code "72") (name "unconnected-(U2-R232-Pad15)") (class "Default")
      (node (ref "U2") (pin "15") (pinfunction "R232_15") (pintype "bidirectional"))
    )
    (net (code "73") (name "unconnected-(U2-~{CTS}-Pad9)") (class "Default")
      (node (ref "U2") (pin "9") (pinfunction "~{CTS}_9") (pintype "bidirectional"))
    )
    (net (code "74") (name "unconnected-(U2-~{DCD}-Pad12)") (class "Default")
      (node (ref "U2") (pin "12") (pinfunction "~{DCD}_12") (pintype "bidirectional"))
    )
    (net (code "75") (name "unconnected-(U2-~{DSR}-Pad10)") (class "Default")
      (node (ref "U2") (pin "10") (pinfunction "~{DSR}_10") (pintype "bidirectional"))
    )
    (net (code "76") (name "unconnected-(U2-~{RI}-Pad11)") (class "Default")
      (node (ref "U2") (pin "11") (pinfunction "~{RI}_11") (pintype "bidirectional"))
    )
    (net (code "77") (name "unconnected-(U3-SCK{slash}CLK-Pad20)") (class "Default")
      (node (ref "U3") (pin "20") (pinfunction "SCK/CLK_20") (pintype "bidirectional"))
    )
    (net (code "78") (name "unconnected-(U3-SCS{slash}CMD-Pad19)") (class "Default")
      (node (ref "U3") (pin "19") (pinfunction "SCS/CMD_19") (pintype "bidirectional"))
    )
    (net (code "79") (name "unconnected-(U3-SDI{slash}SD1-Pad22)") (class "Default")
      (node (ref "U3") (pin "22") (pinfunction "SDI/SD1_22") (pintype "bidirectional"))
    )
    (net (code "80") (name "unconnected-(U3-SDO{slash}SD0-Pad21)") (class "Default")
      (node (ref "U3") (pin "21") (pinfunction "SDO/SD0_21") (pintype "bidirectional"))
    )
    (net (code "81") (name "unconnected-(U3-SENSOR_VN-Pad5)") (class "Default")
      (node (ref "U3") (pin "5") (pinfunction "SENSOR_VN_5") (pintype "input"))
    )
    (net (code "82") (name "unconnected-(U3-SENSOR_VP-Pad4)") (class "Default")
      (node (ref "U3") (pin "4") (pinfunction "SENSOR_VP_4") (pintype "input"))
    )
    (net (code "83") (name "unconnected-(U3-SHD{slash}SD2-Pad17)") (class "Default")
      (node (ref "U3") (pin "17") (pinfunction "SHD/SD2_17") (pintype "bidirectional"))
    )
    (net (code "84") (name "unconnected-(U3-SWP{slash}SD3-Pad18)") (class "Default")
      (node (ref "U3") (pin "18") (pinfunction "SWP/SD3_18") (pintype "bidirectional"))
    )
    (net (code "85") (name "unconnected-(USB1-ID-Pad4)") (class "Default")
      (node (ref "USB1") (pin "4") (pinfunction "ID_4") (pintype "passive"))
    )
  )
)
